# HAB-3_rev1.net
KiCad netlist of a schematic drawn in EAGLE
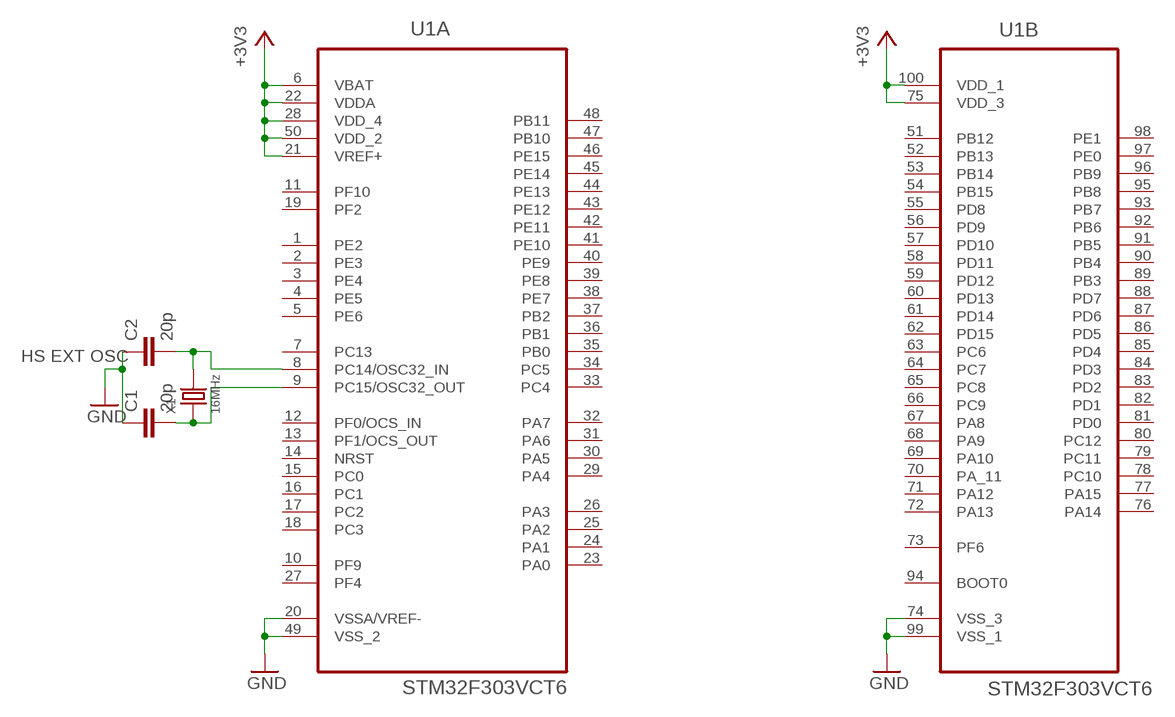
[diagram p0: schematic, sheet 1]

(export (version "E")
  (design (tool "Eeschema 10.0.6"))
  (components
    (comp (ref "C1")
      (value "20p")
      (footprint "eagle-import:C0603")
      (libsource (lib "eagle-import") (part "C-EUC0603"))
    )
    (comp (ref "C2")
      (value "20p")
      (footprint "eagle-import:C0603")
      (libsource (lib "eagle-import") (part "C-EUC0603"))
    )
    (comp (ref "U1")
      (value "STM32F303VCT6")
      (footprint "eagle-import:QFP50P1600X1600X160-100N")
      (libsource (lib "eagle-import") (part "STM32F303VCT6"))
    )
    (comp (ref "X1")
      (value "16MHz")
      (footprint "eagle-import:X4-SMD-3.2X2.5X0.7MM")
      (libsource (lib "eagle-import") (part "CRYSTAL'3225'"))
    )
  )
  (nets
    (net (code "1") (name "+3V3") (class "Default")
      (node (ref "U1") (pin "100") (pinfunction "VDD_1_100") (pintype "power_in"))
      (node (ref "U1") (pin "21") (pinfunction "VREF+_21") (pintype "power_in"))
      (node (ref "U1") (pin "22") (pinfunction "VDDA_22") (pintype "power_in"))
      (node (ref "U1") (pin "28") (pinfunction "VDD_4_28") (pintype "power_in"))
      (node (ref "U1") (pin "50") (pinfunction "VDD_2_50") (pintype "power_in"))
      (node (ref "U1") (pin "6") (pinfunction "VBAT_6") (pintype "power_in"))
      (node (ref "U1") (pin "75") (pinfunction "VDD_3_75") (pintype "power_in"))
    )
    (net (code "2") (name "/PF2") (class "Default")
      (node (ref "U1") (pin "19") (pinfunction "PF2_19") (pintype "power_in"))
    )
    (net (code "3") (name "GND") (class "Default")
      (node (ref "C1") (pin "1") (pinfunction "1_1") (pintype "passive"))
      (node (ref "C2") (pin "1") (pinfunction "1_1") (pintype "passive"))
      (node (ref "U1") (pin "20") (pinfunction "VSSA/VREF-_20") (pintype "passive"))
      (node (ref "U1") (pin "49") (pinfunction "VSS_2_49") (pintype "power_in"))
      (node (ref "U1") (pin "74") (pinfunction "VSS_3_74") (pintype "passive"))
      (node (ref "U1") (pin "99") (pinfunction "VSS_1_99") (pintype "passive"))
    )
    (net (code "4") (name "Net-(U1A-PC14{slash}OSC32_IN)") (class "Default")
      (node (ref "C2") (pin "2") (pinfunction "2_2") (pintype "passive"))
      (node (ref "U1") (pin "8") (pinfunction "PC14/OSC32_IN_8") (pintype "bidirectional"))
      (node (ref "X1") (pin "3") (pinfunction "2_3") (pintype "passive"))
    )
    (net (code "5") (name "Net-(U1A-PC15{slash}OSC32_OUT)") (class "Default")
      (node (ref "C1") (pin "2") (pinfunction "2_2") (pintype "passive"))
      (node (ref "U1") (pin "9") (pinfunction "PC15/OSC32_OUT_9") (pintype "bidirectional"))
      (node (ref "X1") (pin "1") (pinfunction "1_1") (pintype "passive"))
    )
    (net (code "6") (name "unconnected-(U1A-NRST-Pad14)") (class "Default")
      (node (ref "U1") (pin "14") (pinfunction "NRST_14") (pintype "bidirectional"))
    )
    (net (code "7") (name "unconnected-(U1A-PA0-Pad23)") (class "Default")
      (node (ref "U1") (pin "23") (pinfunction "PA0_23") (pintype "bidirectional"))
    )
    (net (code "8") (name "unconnected-(U1A-PA1-Pad24)") (class "Default")
      (node (ref "U1") (pin "24") (pinfunction "PA1_24") (pintype "bidirectional"))
    )
    (net (code "9") (name "unconnected-(U1A-PA2-Pad25)") (class "Default")
      (node (ref "U1") (pin "25") (pinfunction "PA2_25") (pintype "bidirectional"))
    )
    (net (code "10") (name "unconnected-(U1A-PA3-Pad26)") (class "Default")
      (node (ref "U1") (pin "26") (pinfunction "PA3_26") (pintype "bidirectional"))
    )
    (net (code "11") (name "unconnected-(U1A-PA4-Pad29)") (class "Default")
      (node (ref "U1") (pin "29") (pinfunction "PA4_29") (pintype "bidirectional"))
    )
    (net (code "12") (name "unconnected-(U1A-PA5-Pad30)") (class "Default")
      (node (ref "U1") (pin "30") (pinfunction "PA5_30") (pintype "bidirectional"))
    )
    (net (code "13") (name "unconnected-(U1A-PA6-Pad31)") (class "Default")
      (node (ref "U1") (pin "31") (pinfunction "PA6_31") (pintype "bidirectional"))
    )
    (net (code "14") (name "unconnected-(U1A-PA7-Pad32)") (class "Default")
      (node (ref "U1") (pin "32") (pinfunction "PA7_32") (pintype "bidirectional"))
    )
    (net (code "15") (name "unconnected-(U1A-PB0-Pad35)") (class "Default")
      (node (ref "U1") (pin "35") (pinfunction "PB0_35") (pintype "bidirectional"))
    )
    (net (code "16") (name "unconnected-(U1A-PB1-Pad36)") (class "Default")
      (node (ref "U1") (pin "36") (pinfunction "PB1_36") (pintype "bidirectional"))
    )
    (net (code "17") (name "unconnected-(U1A-PB2-Pad37)") (class "Default")
      (node (ref "U1") (pin "37") (pinfunction "PB2_37") (pintype "bidirectional"))
    )
    (net (code "18") (name "unconnected-(U1A-PB10-Pad47)") (class "Default")
      (node (ref "U1") (pin "47") (pinfunction "PB10_47") (pintype "bidirectional"))
    )
    (net (code "19") (name "unconnected-(U1A-PB11-Pad48)") (class "Default")
      (node (ref "U1") (pin "48") (pinfunction "PB11_48") (pintype "bidirectional"))
    )
    (net (code "20") (name "unconnected-(U1A-PC0-Pad15)") (class "Default")
      (node (ref "U1") (pin "15") (pinfunction "PC0_15") (pintype "bidirectional"))
    )
    (net (code "21") (name "unconnected-(U1A-PC1-Pad16)") (class "Default")
      (node (ref "U1") (pin "16") (pinfunction "PC1_16") (pintype "bidirectional"))
    )
    (net (code "22") (name "unconnected-(U1A-PC2-Pad17)") (class "Default")
      (node (ref "U1") (pin "17") (pinfunction "PC2_17") (pintype "bidirectional"))
    )
    (net (code "23") (name "unconnected-(U1A-PC3-Pad18)") (class "Default")
      (node (ref "U1") (pin "18") (pinfunction "PC3_18") (pintype "bidirectional"))
    )
    (net (code "24") (name "unconnected-(U1A-PC4-Pad33)") (class "Default")
      (node (ref "U1") (pin "33") (pinfunction "PC4_33") (pintype "bidirectional"))
    )
    (net (code "25") (name "unconnected-(U1A-PC5-Pad34)") (class "Default")
      (node (ref "U1") (pin "34") (pinfunction "PC5_34") (pintype "bidirectional"))
    )
    (net (code "26") (name "unconnected-(U1A-PC13-Pad7)") (class "Default")
      (node (ref "U1") (pin "7") (pinfunction "PC13_7") (pintype "bidirectional"))
    )
    (net (code "27") (name "unconnected-(U1A-PE2-Pad1)") (class "Default")
      (node (ref "U1") (pin "1") (pinfunction "PE2_1") (pintype "bidirectional"))
    )
    (net (code "28") (name "unconnected-(U1A-PE3-Pad2)") (class "Default")
      (node (ref "U1") (pin "2") (pinfunction "PE3_2") (pintype "bidirectional"))
    )
    (net (code "29") (name "unconnected-(U1A-PE4-Pad3)") (class "Default")
      (node (ref "U1") (pin "3") (pinfunction "PE4_3") (pintype "bidirectional"))
    )
    (net (code "30") (name "unconnected-(U1A-PE5-Pad4)") (class "Default")
      (node (ref "U1") (pin "4") (pinfunction "PE5_4") (pintype "bidirectional"))
    )
    (net (code "31") (name "unconnected-(U1A-PE6-Pad5)") (class "Default")
      (node (ref "U1") (pin "5") (pinfunction "PE6_5") (pintype "bidirectional"))
    )
    (net (code "32") (name "unconnected-(U1A-PE7-Pad38)") (class "Default")
      (node (ref "U1") (pin "38") (pinfunction "PE7_38") (pintype "bidirectional"))
    )
    (net (code "33") (name "unconnected-(U1A-PE8-Pad39)") (class "Default")
      (node (ref "U1") (pin "39") (pinfunction "PE8_39") (pintype "bidirectional"))
    )
    (net (code "34") (name "unconnected-(U1A-PE9-Pad40)") (class "Default")
      (node (ref "U1") (pin "40") (pinfunction "PE9_40") (pintype "bidirectional"))
    )
    (net (code "35") (name "unconnected-(U1A-PE10-Pad41)") (class "Default")
      (node (ref "U1") (pin "41") (pinfunction "PE10_41") (pintype "bidirectional"))
    )
    (net (code "36") (name "unconnected-(U1A-PE11-Pad42)") (class "Default")
      (node (ref "U1") (pin "42") (pinfunction "PE11_42") (pintype "bidirectional"))
    )
    (net (code "37") (name "unconnected-(U1A-PE12-Pad43)") (class "Default")
      (node (ref "U1") (pin "43") (pinfunction "PE12_43") (pintype "bidirectional"))
    )
    (net (code "38") (name "unconnected-(U1A-PE13-Pad44)") (class "Default")
      (node (ref "U1") (pin "44") (pinfunction "PE13_44") (pintype "bidirectional"))
    )
    (net (code "39") (name "unconnected-(U1A-PE14-Pad45)") (class "Default")
      (node (ref "U1") (pin "45") (pinfunction "PE14_45") (pintype "bidirectional"))
    )
    (net (code "40") (name "unconnected-(U1A-PE15-Pad46)") (class "Default")
      (node (ref "U1") (pin "46") (pinfunction "PE15_46") (pintype "bidirectional"))
    )
    (net (code "41") (name "unconnected-(U1A-PF0{slash}OCS_IN-Pad12)") (class "Default")
      (node (ref "U1") (pin "12") (pinfunction "PF0/OCS_IN_12") (pintype "bidirectional"))
    )
    (net (code "42") (name "unconnected-(U1A-PF1{slash}OCS_OUT-Pad13)") (class "Default")
      (node (ref "U1") (pin "13") (pinfunction "PF1/OCS_OUT_13") (pintype "bidirectional"))
    )
    (net (code "43") (name "unconnected-(U1A-PF4-Pad27)") (class "Default")
      (node (ref "U1") (pin "27") (pinfunction "PF4_27") (pintype "bidirectional"))
    )
    (net (code "44") (name "unconnected-(U1A-PF9-Pad10)") (class "Default")
      (node (ref "U1") (pin "10") (pinfunction "PF9_10") (pintype "bidirectional"))
    )
    (net (code "45") (name "unconnected-(U1A-PF10-Pad11)") (class "Default")
      (node (ref "U1") (pin "11") (pinfunction "PF10_11") (pintype "bidirectional"))
    )
    (net (code "46") (name "unconnected-(U1B-BOOT0-Pad94)") (class "Default")
      (node (ref "U1") (pin "94") (pinfunction "BOOT0_94") (pintype "input"))
    )
    (net (code "47") (name "unconnected-(U1B-PA8-Pad67)") (class "Default")
      (node (ref "U1") (pin "67") (pinfunction "PA8_67") (pintype "bidirectional"))
    )
    (net (code "48") (name "unconnected-(U1B-PA9-Pad68)") (class "Default")
      (node (ref "U1") (pin "68") (pinfunction "PA9_68") (pintype "bidirectional"))
    )
    (net (code "49") (name "unconnected-(U1B-PA10-Pad69)") (class "Default")
      (node (ref "U1") (pin "69") (pinfunction "PA10_69") (pintype "bidirectional"))
    )
    (net (code "50") (name "unconnected-(U1B-PA12-Pad71)") (class "Default")
      (node (ref "U1") (pin "71") (pinfunction "PA12_71") (pintype "bidirectional"))
    )
    (net (code "51") (name "unconnected-(U1B-PA13-Pad72)") (class "Default")
      (node (ref "U1") (pin "72") (pinfunction "PA13_72") (pintype "bidirectional"))
    )
    (net (code "52") (name "unconnected-(U1B-PA14-Pad76)") (class "Default")
      (node (ref "U1") (pin "76") (pinfunction "PA14_76") (pintype "bidirectional"))
    )
    (net (code "53") (name "unconnected-(U1B-PA15-Pad77)") (class "Default")
      (node (ref "U1") (pin "77") (pinfunction "PA15_77") (pintype "bidirectional"))
    )
    (net (code "54") (name "unconnected-(U1B-PA_11-Pad70)") (class "Default")
      (node (ref "U1") (pin "70") (pinfunction "PA_11_70") (pintype "bidirectional"))
    )
    (net (code "55") (name "unconnected-(U1B-PB3-Pad89)") (class "Default")
      (node (ref "U1") (pin "89") (pinfunction "PB3_89") (pintype "bidirectional"))
    )
    (net (code "56") (name "unconnected-(U1B-PB4-Pad90)") (class "Default")
      (node (ref "U1") (pin "90") (pinfunction "PB4_90") (pintype "bidirectional"))
    )
    (net (code "57") (name "unconnected-(U1B-PB5-Pad91)") (class "Default")
      (node (ref "U1") (pin "91") (pinfunction "PB5_91") (pintype "bidirectional"))
    )
    (net (code "58") (name "unconnected-(U1B-PB6-Pad92)") (class "Default")
      (node (ref "U1") (pin "92") (pinfunction "PB6_92") (pintype "bidirectional"))
    )
    (net (code "59") (name "unconnected-(U1B-PB7-Pad93)") (class "Default")
      (node (ref "U1") (pin "93") (pinfunction "PB7_93") (pintype "bidirectional"))
    )
    (net (code "60") (name "unconnected-(U1B-PB8-Pad95)") (class "Default")
      (node (ref "U1") (pin "95") (pinfunction "PB8_95") (pintype "bidirectional"))
    )
    (net (code "61") (name "unconnected-(U1B-PB9-Pad96)") (class "Default")
      (node (ref "U1") (pin "96") (pinfunction "PB9_96") (pintype "bidirectional"))
    )
    (net (code "62") (name "unconnected-(U1B-PB12-Pad51)") (class "Default")
      (node (ref "U1") (pin "51") (pinfunction "PB12_51") (pintype "bidirectional"))
    )
    (net (code "63") (name "unconnected-(U1B-PB13-Pad52)") (class "Default")
      (node (ref "U1") (pin "52") (pinfunction "PB13_52") (pintype "bidirectional"))
    )
    (net (code "64") (name "unconnected-(U1B-PB14-Pad53)") (class "Default")
      (node (ref "U1") (pin "53") (pinfunction "PB14_53") (pintype "bidirectional"))
    )
    (net (code "65") (name "unconnected-(U1B-PB15-Pad54)") (class "Default")
      (node (ref "U1") (pin "54") (pinfunction "PB15_54") (pintype "bidirectional"))
    )
    (net (code "66") (name "unconnected-(U1B-PC6-Pad63)") (class "Default")
      (node (ref "U1") (pin "63") (pinfunction "PC6_63") (pintype "bidirectional"))
    )
    (net (code "67") (name "unconnected-(U1B-PC7-Pad64)") (class "Default")
      (node (ref "U1") (pin "64") (pinfunction "PC7_64") (pintype "bidirectional"))
    )
    (net (code "68") (name "unconnected-(U1B-PC8-Pad65)") (class "Default")
      (node (ref "U1") (pin "65") (pinfunction "PC8_65") (pintype "bidirectional"))
    )
    (net (code "69") (name "unconnected-(U1B-PC9-Pad66)") (class "Default")
      (node (ref "U1") (pin "66") (pinfunction "PC9_66") (pintype "bidirectional"))
    )
    (net (code "70") (name "unconnected-(U1B-PC10-Pad78)") (class "Default")
      (node (ref "U1") (pin "78") (pinfunction "PC10_78") (pintype "bidirectional"))
    )
    (net (code "71") (name "unconnected-(U1B-PC11-Pad79)") (class "Default")
      (node (ref "U1") (pin "79") (pinfunction "PC11_79") (pintype "bidirectional"))
    )
    (net (code "72") (name "unconnected-(U1B-PC12-Pad80)") (class "Default")
      (node (ref "U1") (pin "80") (pinfunction "PC12_80") (pintype "bidirectional"))
    )
    (net (code "73") (name "unconnected-(U1B-PD0-Pad81)") (class "Default")
      (node (ref "U1") (pin "81") (pinfunction "PD0_81") (pintype "bidirectional"))
    )
    (net (code "74") (name "unconnected-(U1B-PD1-Pad82)") (class "Default")
      (node (ref "U1") (pin "82") (pinfunction "PD1_82") (pintype "bidirectional"))
    )
    (net (code "75") (name "unconnected-(U1B-PD2-Pad83)") (class "Default")
      (node (ref "U1") (pin "83") (pinfunction "PD2_83") (pintype "bidirectional"))
    )
    (net (code "76") (name "unconnected-(U1B-PD3-Pad84)") (class "Default")
      (node (ref "U1") (pin "84") (pinfunction "PD3_84") (pintype "bidirectional"))
    )
    (net (code "77") (name "unconnected-(U1B-PD4-Pad85)") (class "Default")
      (node (ref "U1") (pin "85") (pinfunction "PD4_85") (pintype "bidirectional"))
    )
    (net (code "78") (name "unconnected-(U1B-PD5-Pad86)") (class "Default")
      (node (ref "U1") (pin "86") (pinfunction "PD5_86") (pintype "bidirectional"))
    )
    (net (code "79") (name "unconnected-(U1B-PD6-Pad87)") (class "Default")
      (node (ref "U1") (pin "87") (pinfunction "PD6_87") (pintype "bidirectional"))
    )
    (net (code "80") (name "unconnected-(U1B-PD7-Pad88)") (class "Default")
      (node (ref "U1") (pin "88") (pinfunction "PD7_88") (pintype "bidirectional"))
    )
    (net (code "81") (name "unconnected-(U1B-PD8-Pad55)") (class "Default")
      (node (ref "U1") (pin "55") (pinfunction "PD8_55") (pintype "bidirectional"))
    )
    (net (code "82") (name "unconnected-(U1B-PD9-Pad56)") (class "Default")
      (node (ref "U1") (pin "56") (pinfunction "PD9_56") (pintype "bidirectional"))
    )
    (net (code "83") (name "unconnected-(U1B-PD10-Pad57)") (class "Default")
      (node (ref "U1") (pin "57") (pinfunction "PD10_57") (pintype "bidirectional"))
    )
    (net (code "84") (name "unconnected-(U1B-PD11-Pad58)") (class "Default")
      (node (ref "U1") (pin "58") (pinfunction "PD11_58") (pintype "bidirectional"))
    )
    (net (code "85") (name "unconnected-(U1B-PD12-Pad59)") (class "Default")
      (node (ref "U1") (pin "59") (pinfunction "PD12_59") (pintype "bidirectional"))
    )
    (net (code "86") (name "unconnected-(U1B-PD13-Pad60)") (class "Default")
      (node (ref "U1") (pin "60") (pinfunction "PD13_60") (pintype "bidirectional"))
    )
    (net (code "87") (name "unconnected-(U1B-PD14-Pad61)") (class "Default")
      (node (ref "U1") (pin "61") (pinfunction "PD14_61") (pintype "bidirectional"))
    )
    (net (code "88") (name "unconnected-(U1B-PD15-Pad62)") (class "Default")
      (node (ref "U1") (pin "62") (pinfunction "PD15_62") (pintype "bidirectional"))
    )
    (net (code "89") (name "unconnected-(U1B-PE0-Pad97)") (class "Default")
      (node (ref "U1") (pin "97") (pinfunction "PE0_97") (pintype "bidirectional"))
    )
    (net (code "90") (name "unconnected-(U1B-PE1-Pad98)") (class "Default")
      (node (ref "U1") (pin "98") (pinfunction "PE1_98") (pintype "bidirectional"))
    )
    (net (code "91") (name "unconnected-(U1B-PF6-Pad73)") (class "Default")
      (node (ref "U1") (pin "73") (pinfunction "PF6_73") (pintype "bidirectional"))
    )
  )
)
